# wifilights-shim.net
KiCad netlist of a schematic drawn in EAGLE
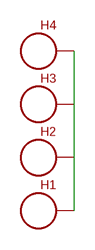
[diagram p0: schematic, sheet 1]

(export (version "E")
  (design (tool "Eeschema 10.0.6"))
  (components
    (comp (ref "H1")
      (value "SEW_HOLE")
      (footprint "eagle-import:SIMPLE_HOLE")
      (libsource (lib "eagle-import") (part "SEW_HOLE"))
    )
    (comp (ref "H2")
      (value "SEW_HOLE")
      (footprint "eagle-import:SIMPLE_HOLE")
      (libsource (lib "eagle-import") (part "SEW_HOLE"))
    )
    (comp (ref "H3")
      (value "SEW_HOLE")
      (footprint "eagle-import:SIMPLE_HOLE")
      (libsource (lib "eagle-import") (part "SEW_HOLE"))
    )
    (comp (ref "H4")
      (value "SEW_HOLE")
      (footprint "eagle-import:SIMPLE_HOLE")
      (libsource (lib "eagle-import") (part "SEW_HOLE"))
    )
  )
  (nets
    (net (code "1") (name "Net-(H1-PadP$1)") (class "Default")
      (node (ref "H1") (pin "P$1") (pinfunction "P$1_P$1") (pintype "bidirectional"))
      (node (ref "H2") (pin "P$1") (pinfunction "P$1_P$1") (pintype "bidirectional"))
      (node (ref "H3") (pin "P$1") (pinfunction "P$1_P$1") (pintype "bidirectional"))
      (node (ref "H4") (pin "P$1") (pinfunction "P$1_P$1") (pintype "bidirectional"))
    )
  )
)
